# signal_test.net
KiCad netlist of a schematic drawn in EAGLE
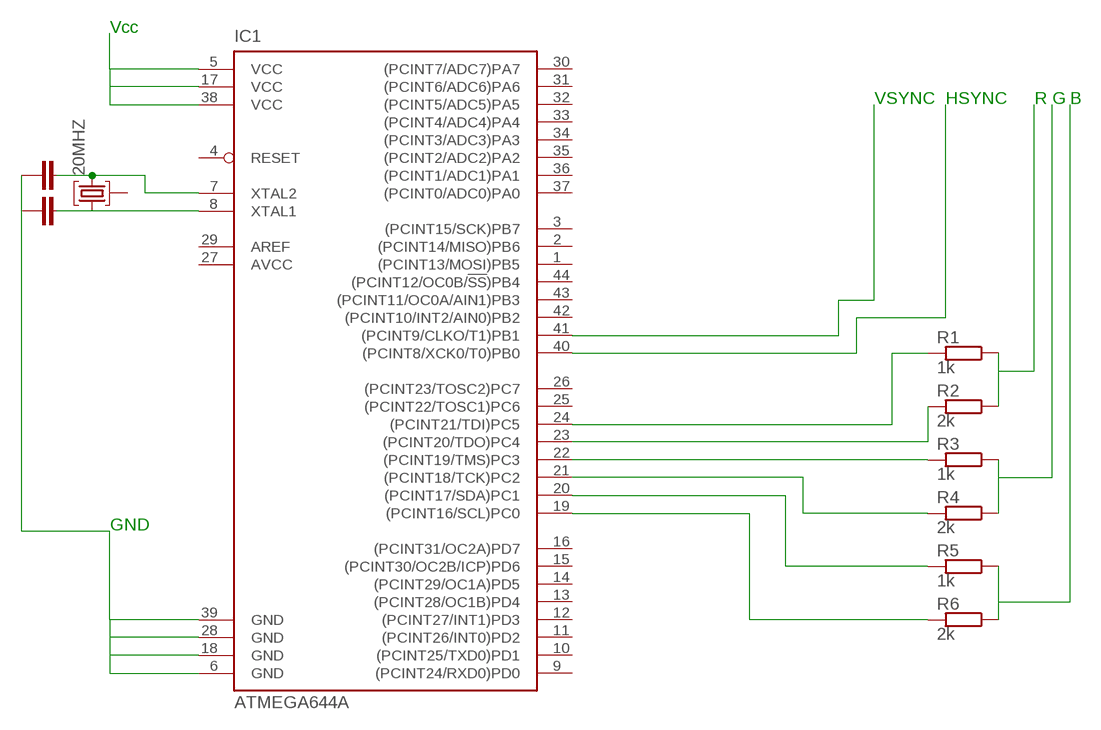
[diagram p0: schematic, sheet 1]

(export (version "E")
  (design (tool "Eeschema 10.0.6"))
  (components
    (comp (ref "20MHZ")
      (value "12M10AHC49HT")
      (footprint "eagle-import:HC49U")
      (libsource (lib "eagle-import") (part "12M10AHC49HT"))
    )
    (comp (ref "IC1")
      (value "ATMEGA644A")
      (footprint "eagle-import:TQFP44")
      (fields (field (name "MPN") "ATMEGA644PV-10AU"))
      (libsource (lib "eagle-import") (part "ATMEGA644A"))
    )
    (comp (ref "R1")
      (value "1k")
      (footprint "eagle-import:BVS")
      (libsource (lib "eagle-import") (part "BVS"))
    )
    (comp (ref "R2")
      (value "2k")
      (footprint "eagle-import:BVS")
      (libsource (lib "eagle-import") (part "BVS"))
    )
    (comp (ref "R3")
      (value "1k")
      (footprint "eagle-import:BVS")
      (libsource (lib "eagle-import") (part "BVS"))
    )
    (comp (ref "R4")
      (value "2k")
      (footprint "eagle-import:BVS")
      (libsource (lib "eagle-import") (part "BVS"))
    )
    (comp (ref "R5")
      (value "1k")
      (footprint "eagle-import:BVS")
      (libsource (lib "eagle-import") (part "BVS"))
    )
    (comp (ref "R6")
      (value "2k")
      (footprint "eagle-import:BVS")
      (libsource (lib "eagle-import") (part "BVS"))
    )
  )
  (nets
    (net (code "1") (name "/AVCC") (class "Default")
      (node (ref "IC1") (pin "27") (pinfunction "AVCC_27") (pintype "power_in"))
    )
    (net (code "2") (name "Net-(IC1-(PCINT16{slash}SCL)PC0)") (class "Default")
      (node (ref "IC1") (pin "19") (pinfunction "(PCINT16/SCL)PC0_19") (pintype "output"))
      (node (ref "R6") (pin "2") (pinfunction "2_2") (pintype "passive"))
    )
    (net (code "3") (name "Net-(IC1-(PCINT17{slash}SDA)PC1)") (class "Default")
      (node (ref "IC1") (pin "20") (pinfunction "(PCINT17/SDA)PC1_20") (pintype "output"))
      (node (ref "R5") (pin "2") (pinfunction "2_2") (pintype "passive"))
    )
    (net (code "4") (name "Net-(IC1-(PCINT18{slash}TCK)PC2)") (class "Default")
      (node (ref "IC1") (pin "21") (pinfunction "(PCINT18/TCK)PC2_21") (pintype "output"))
      (node (ref "R4") (pin "2") (pinfunction "2_2") (pintype "passive"))
    )
    (net (code "5") (name "Net-(IC1-(PCINT19{slash}TMS)PC3)") (class "Default")
      (node (ref "IC1") (pin "22") (pinfunction "(PCINT19/TMS)PC3_22") (pintype "output"))
      (node (ref "R3") (pin "2") (pinfunction "2_2") (pintype "passive"))
    )
    (net (code "6") (name "Net-(IC1-(PCINT20{slash}TDO)PC4)") (class "Default")
      (node (ref "IC1") (pin "23") (pinfunction "(PCINT20/TDO)PC4_23") (pintype "output"))
      (node (ref "R2") (pin "2") (pinfunction "2_2") (pintype "passive"))
    )
    (net (code "7") (name "Net-(IC1-(PCINT21{slash}TDI)PC5)") (class "Default")
      (node (ref "IC1") (pin "24") (pinfunction "(PCINT21/TDI)PC5_24") (pintype "output"))
      (node (ref "R1") (pin "2") (pinfunction "2_2") (pintype "passive"))
    )
    (net (code "8") (name "Net-(IC1-GND-Pad18)") (class "Default")
      (node (ref "IC1") (pin "18") (pinfunction "GND_18") (pintype "power_in"))
      (node (ref "IC1") (pin "28") (pinfunction "GND_28") (pintype "power_in"))
      (node (ref "IC1") (pin "39") (pinfunction "GND_39") (pintype "power_in"))
      (node (ref "IC1") (pin "6") (pinfunction "GND_6") (pintype "power_in"))
    )
    (net (code "9") (name "Net-(IC1-VCC-Pad17)") (class "Default")
      (node (ref "IC1") (pin "17") (pinfunction "VCC_17") (pintype "power_in"))
      (node (ref "IC1") (pin "38") (pinfunction "VCC_38") (pintype "power_in"))
      (node (ref "IC1") (pin "5") (pinfunction "VCC_5") (pintype "power_in"))
    )
    (net (code "10") (name "Net-(IC1-XTAL2)") (class "Default")
      (node (ref "20MHZ") (pin "3") (pinfunction "3_3") (pintype "passive"))
      (node (ref "IC1") (pin "7") (pinfunction "XTAL2_7") (pintype "bidirectional"))
    )
    (net (code "11") (name "Net-(R1-Pad1)") (class "Default")
      (node (ref "R1") (pin "1") (pinfunction "1_1") (pintype "passive"))
      (node (ref "R2") (pin "1") (pinfunction "1_1") (pintype "passive"))
    )
    (net (code "12") (name "Net-(R3-Pad1)") (class "Default")
      (node (ref "R3") (pin "1") (pinfunction "1_1") (pintype "passive"))
      (node (ref "R4") (pin "1") (pinfunction "1_1") (pintype "passive"))
    )
    (net (code "13") (name "Net-(R5-Pad1)") (class "Default")
      (node (ref "R5") (pin "1") (pinfunction "1_1") (pintype "passive"))
      (node (ref "R6") (pin "1") (pinfunction "1_1") (pintype "passive"))
    )
    (net (code "14") (name "unconnected-(20MHZ-Pad1)") (class "Default")
      (node (ref "20MHZ") (pin "1") (pinfunction "1_1") (pintype "passive"))
    )
    (net (code "15") (name "unconnected-(20MHZ-Pad2)") (class "Default")
      (node (ref "20MHZ") (pin "2") (pinfunction "2_2") (pintype "passive"))
    )
    (net (code "16") (name "unconnected-(IC1-(PCINT0{slash}ADC0)PA0-Pad37)") (class "Default")
      (node (ref "IC1") (pin "37") (pinfunction "(PCINT0/ADC0)PA0_37") (pintype "bidirectional"))
    )
    (net (code "17") (name "unconnected-(IC1-(PCINT1{slash}ADC1)PA1-Pad36)") (class "Default")
      (node (ref "IC1") (pin "36") (pinfunction "(PCINT1/ADC1)PA1_36") (pintype "bidirectional"))
    )
    (net (code "18") (name "unconnected-(IC1-(PCINT2{slash}ADC2)PA2-Pad35)") (class "Default")
      (node (ref "IC1") (pin "35") (pinfunction "(PCINT2/ADC2)PA2_35") (pintype "bidirectional"))
    )
    (net (code "19") (name "unconnected-(IC1-(PCINT3{slash}ADC3)PA3-Pad34)") (class "Default")
      (node (ref "IC1") (pin "34") (pinfunction "(PCINT3/ADC3)PA3_34") (pintype "bidirectional"))
    )
    (net (code "20") (name "unconnected-(IC1-(PCINT4{slash}ADC4)PA4-Pad33)") (class "Default")
      (node (ref "IC1") (pin "33") (pinfunction "(PCINT4/ADC4)PA4_33") (pintype "bidirectional"))
    )
    (net (code "21") (name "unconnected-(IC1-(PCINT5{slash}ADC5)PA5-Pad32)") (class "Default")
      (node (ref "IC1") (pin "32") (pinfunction "(PCINT5/ADC5)PA5_32") (pintype "bidirectional"))
    )
    (net (code "22") (name "unconnected-(IC1-(PCINT6{slash}ADC6)PA6-Pad31)") (class "Default")
      (node (ref "IC1") (pin "31") (pinfunction "(PCINT6/ADC6)PA6_31") (pintype "bidirectional"))
    )
    (net (code "23") (name "unconnected-(IC1-(PCINT7{slash}ADC7)PA7-Pad30)") (class "Default")
      (node (ref "IC1") (pin "30") (pinfunction "(PCINT7/ADC7)PA7_30") (pintype "bidirectional"))
    )
    (net (code "24") (name "unconnected-(IC1-(PCINT8{slash}XCK0{slash}T0)PB0-Pad40)") (class "Default")
      (node (ref "IC1") (pin "40") (pinfunction "(PCINT8/XCK0/T0)PB0_40") (pintype "bidirectional"))
    )
    (net (code "25") (name "unconnected-(IC1-(PCINT9{slash}CLKO{slash}T1)PB1-Pad41)") (class "Default")
      (node (ref "IC1") (pin "41") (pinfunction "(PCINT9/CLKO/T1)PB1_41") (pintype "bidirectional"))
    )
    (net (code "26") (name "unconnected-(IC1-(PCINT10{slash}INT2{slash}AIN0)PB2-Pad42)") (class "Default")
      (node (ref "IC1") (pin "42") (pinfunction "(PCINT10/INT2/AIN0)PB2_42") (pintype "bidirectional"))
    )
    (net (code "27") (name "unconnected-(IC1-(PCINT11{slash}OC0A{slash}AIN1)PB3-Pad43)") (class "Default")
      (node (ref "IC1") (pin "43") (pinfunction "(PCINT11/OC0A/AIN1)PB3_43") (pintype "bidirectional"))
    )
    (net (code "28") (name "unconnected-(IC1-(PCINT12{slash}OC0B{slash}~{SS})PB4-Pad44)") (class "Default")
      (node (ref "IC1") (pin "44") (pinfunction "(PCINT12/OC0B/~{SS})PB4_44") (pintype "bidirectional"))
    )
    (net (code "29") (name "unconnected-(IC1-(PCINT13{slash}MOSI)PB5-Pad1)") (class "Default")
      (node (ref "IC1") (pin "1") (pinfunction "(PCINT13/MOSI)PB5_1") (pintype "bidirectional"))
    )
    (net (code "30") (name "unconnected-(IC1-(PCINT14{slash}MISO)PB6-Pad2)") (class "Default")
      (node (ref "IC1") (pin "2") (pinfunction "(PCINT14/MISO)PB6_2") (pintype "bidirectional"))
    )
    (net (code "31") (name "unconnected-(IC1-(PCINT15{slash}SCK)PB7-Pad3)") (class "Default")
      (node (ref "IC1") (pin "3") (pinfunction "(PCINT15/SCK)PB7_3") (pintype "bidirectional"))
    )
    (net (code "32") (name "unconnected-(IC1-(PCINT22{slash}TOSC1)PC6-Pad25)") (class "Default")
      (node (ref "IC1") (pin "25") (pinfunction "(PCINT22/TOSC1)PC6_25") (pintype "output"))
    )
    (net (code "33") (name "unconnected-(IC1-(PCINT23{slash}TOSC2)PC7-Pad26)") (class "Default")
      (node (ref "IC1") (pin "26") (pinfunction "(PCINT23/TOSC2)PC7_26") (pintype "output"))
    )
    (net (code "34") (name "unconnected-(IC1-(PCINT24{slash}RXD0)PD0-Pad9)") (class "Default")
      (node (ref "IC1") (pin "9") (pinfunction "(PCINT24/RXD0)PD0_9") (pintype "bidirectional"))
    )
    (net (code "35") (name "unconnected-(IC1-(PCINT25{slash}TXD0)PD1-Pad10)") (class "Default")
      (node (ref "IC1") (pin "10") (pinfunction "(PCINT25/TXD0)PD1_10") (pintype "bidirectional"))
    )
    (net (code "36") (name "unconnected-(IC1-(PCINT26{slash}INT0)PD2-Pad11)") (class "Default")
      (node (ref "IC1") (pin "11") (pinfunction "(PCINT26/INT0)PD2_11") (pintype "bidirectional"))
    )
    (net (code "37") (name "unconnected-(IC1-(PCINT27{slash}INT1)PD3-Pad12)") (class "Default")
      (node (ref "IC1") (pin "12") (pinfunction "(PCINT27/INT1)PD3_12") (pintype "bidirectional"))
    )
    (net (code "38") (name "unconnected-(IC1-(PCINT28{slash}OC1B)PD4-Pad13)") (class "Default")
      (node (ref "IC1") (pin "13") (pinfunction "(PCINT28/OC1B)PD4_13") (pintype "bidirectional"))
    )
    (net (code "39") (name "unconnected-(IC1-(PCINT29{slash}OC1A)PD5-Pad14)") (class "Default")
      (node (ref "IC1") (pin "14") (pinfunction "(PCINT29/OC1A)PD5_14") (pintype "bidirectional"))
    )
    (net (code "40") (name "unconnected-(IC1-(PCINT30{slash}OC2B{slash}ICP)PD6-Pad15)") (class "Default")
      (node (ref "IC1") (pin "15") (pinfunction "(PCINT30/OC2B/ICP)PD6_15") (pintype "bidirectional"))
    )
    (net (code "41") (name "unconnected-(IC1-(PCINT31{slash}OC2A)PD7-Pad16)") (class "Default")
      (node (ref "IC1") (pin "16") (pinfunction "(PCINT31/OC2A)PD7_16") (pintype "bidirectional"))
    )
    (net (code "42") (name "unconnected-(IC1-AREF-Pad29)") (class "Default")
      (node (ref "IC1") (pin "29") (pinfunction "AREF_29") (pintype "passive"))
    )
    (net (code "43") (name "unconnected-(IC1-RESET-Pad4)") (class "Default")
      (node (ref "IC1") (pin "4") (pinfunction "RESET_4") (pintype "input"))
    )
    (net (code "44") (name "unconnected-(IC1-XTAL1-Pad8)") (class "Default")
      (node (ref "IC1") (pin "8") (pinfunction "XTAL1_8") (pintype "bidirectional"))
    )
  )
)
